# schematic.net
KiCad netlist of a schematic drawn in EAGLE
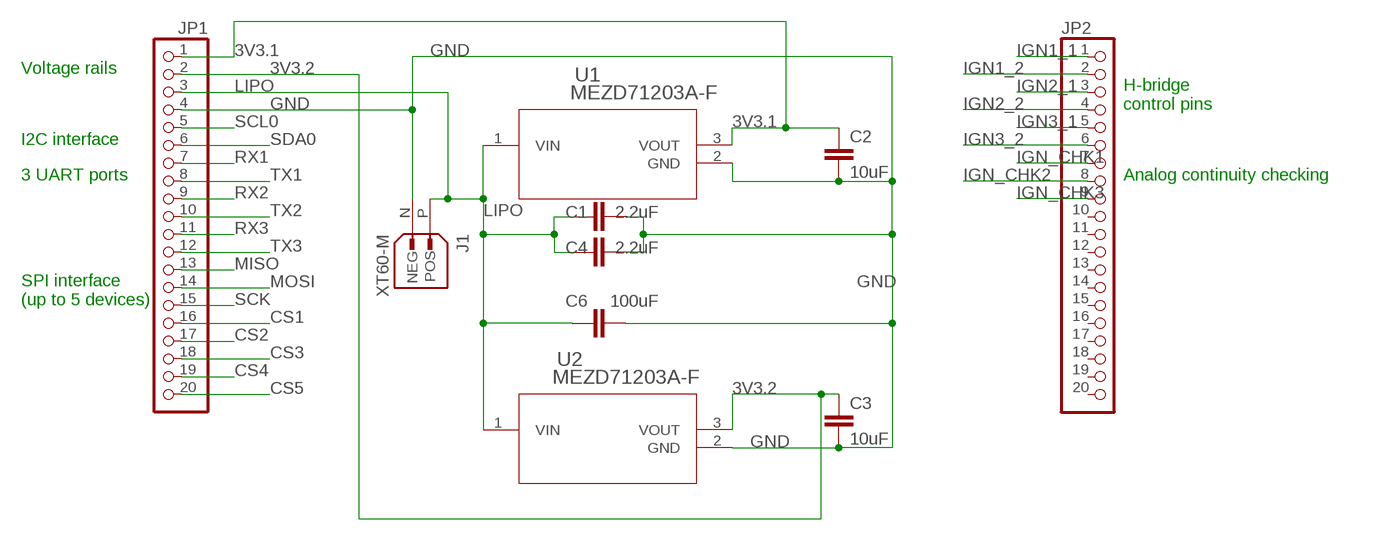
[diagram p0: schematic, sheet 1]

(export (version "E")
  (design (tool "Eeschema 10.0.6"))
  (components
    (comp (ref "C1")
      (value "2.2uF")
      (footprint "eagle-import:C0805")
      (libsource (lib "eagle-import") (part "C-EUC0805"))
    )
    (comp (ref "C2")
      (value "10uF")
      (footprint "eagle-import:C0805")
      (libsource (lib "eagle-import") (part "C-EUC0805"))
    )
    (comp (ref "C3")
      (value "10uF")
      (footprint "eagle-import:C0805")
      (libsource (lib "eagle-import") (part "C-EUC0805"))
    )
    (comp (ref "C4")
      (value "2.2uF")
      (footprint "eagle-import:C0805")
      (libsource (lib "eagle-import") (part "C-EUC0805"))
    )
    (comp (ref "C6")
      (value "100uF")
      (footprint "eagle-import:C0805")
      (libsource (lib "eagle-import") (part "C-EUC0805"))
    )
    (comp (ref "J1")
      (value "XT60-M")
      (footprint "eagle-import:AMASS_XT60-M")
      (fields (field (name "MF") "AMASS"))
      (libsource (lib "eagle-import") (part "XT60-M"))
    )
    (comp (ref "JP1")
      (value "PINHD-1X20")
      (footprint "eagle-import:1X20")
      (libsource (lib "eagle-import") (part "PINHD-1X20"))
    )
    (comp (ref "JP2")
      (value "PINHD-1X20")
      (footprint "eagle-import:1X20")
      (libsource (lib "eagle-import") (part "PINHD-1X20"))
    )
    (comp (ref "U1")
      (value "MEZD71203A-F")
      (footprint "eagle-import:MEZD71203A_MNP")
      (fields (field (name "COPYRIGHT") "Copyright (C) 2022 Ultra Librarian. All rights reserved."))
      (libsource (lib "eagle-import") (part "MEZD71203A-F"))
    )
    (comp (ref "U2")
      (value "MEZD71203A-F")
      (footprint "eagle-import:MEZD71203A_MNP")
      (fields (field (name "COPYRIGHT") "Copyright (C) 2022 Ultra Librarian. All rights reserved."))
      (libsource (lib "eagle-import") (part "MEZD71203A-F"))
    )
  )
  (nets
    (net (code "1") (name "/3V3.1") (class "Default")
      (node (ref "C2") (pin "1") (pinfunction "1_1") (pintype "passive"))
      (node (ref "JP1") (pin "1") (pinfunction "1_1") (pintype "passive"))
      (node (ref "U1") (pin "3") (pinfunction "VOUT_3") (pintype "output"))
    )
    (net (code "2") (name "/3V3.2") (class "Default")
      (node (ref "C3") (pin "1") (pinfunction "1_1") (pintype "passive"))
      (node (ref "JP1") (pin "2") (pinfunction "2_2") (pintype "passive"))
      (node (ref "U2") (pin "3") (pinfunction "VOUT_3") (pintype "output"))
    )
    (net (code "3") (name "/CS1") (class "Default")
      (node (ref "JP1") (pin "16") (pinfunction "16_16") (pintype "passive"))
    )
    (net (code "4") (name "/CS2") (class "Default")
      (node (ref "JP1") (pin "17") (pinfunction "17_17") (pintype "passive"))
    )
    (net (code "5") (name "/CS3") (class "Default")
      (node (ref "JP1") (pin "18") (pinfunction "18_18") (pintype "passive"))
    )
    (net (code "6") (name "/CS4") (class "Default")
      (node (ref "JP1") (pin "19") (pinfunction "19_19") (pintype "passive"))
    )
    (net (code "7") (name "/CS5") (class "Default")
      (node (ref "JP1") (pin "20") (pinfunction "20_20") (pintype "passive"))
    )
    (net (code "8") (name "/GND") (class "Default")
      (node (ref "C1") (pin "2") (pinfunction "2_2") (pintype "passive"))
      (node (ref "C2") (pin "2") (pinfunction "2_2") (pintype "passive"))
      (node (ref "C3") (pin "2") (pinfunction "2_2") (pintype "passive"))
      (node (ref "C4") (pin "2") (pinfunction "2_2") (pintype "passive"))
      (node (ref "C6") (pin "2") (pinfunction "2_2") (pintype "passive"))
      (node (ref "J1") (pin "N") (pinfunction "NEG_N") (pintype "passive"))
      (node (ref "JP1") (pin "4") (pinfunction "4_4") (pintype "passive"))
      (node (ref "U1") (pin "2") (pinfunction "GND_2") (pintype "power_in"))
      (node (ref "U2") (pin "2") (pinfunction "GND_2") (pintype "power_in"))
    )
    (net (code "9") (name "/IGN1_1") (class "Default")
      (node (ref "JP2") (pin "1") (pinfunction "1_1") (pintype "passive"))
    )
    (net (code "10") (name "/IGN1_2") (class "Default")
      (node (ref "JP2") (pin "2") (pinfunction "2_2") (pintype "passive"))
    )
    (net (code "11") (name "/IGN2_1") (class "Default")
      (node (ref "JP2") (pin "3") (pinfunction "3_3") (pintype "passive"))
    )
    (net (code "12") (name "/IGN2_2") (class "Default")
      (node (ref "JP2") (pin "4") (pinfunction "4_4") (pintype "passive"))
    )
    (net (code "13") (name "/IGN3_1") (class "Default")
      (node (ref "JP2") (pin "5") (pinfunction "5_5") (pintype "passive"))
    )
    (net (code "14") (name "/IGN3_2") (class "Default")
      (node (ref "JP2") (pin "6") (pinfunction "6_6") (pintype "passive"))
    )
    (net (code "15") (name "/IGN_CHK1") (class "Default")
      (node (ref "JP2") (pin "7") (pinfunction "7_7") (pintype "passive"))
    )
    (net (code "16") (name "/IGN_CHK2") (class "Default")
      (node (ref "JP2") (pin "8") (pinfunction "8_8") (pintype "passive"))
    )
    (net (code "17") (name "/IGN_CHK3") (class "Default")
      (node (ref "JP2") (pin "9") (pinfunction "9_9") (pintype "passive"))
    )
    (net (code "18") (name "/LIPO") (class "Default")
      (node (ref "C1") (pin "1") (pinfunction "1_1") (pintype "passive"))
      (node (ref "C4") (pin "1") (pinfunction "1_1") (pintype "passive"))
      (node (ref "C6") (pin "1") (pinfunction "1_1") (pintype "passive"))
      (node (ref "J1") (pin "P") (pinfunction "POS_P") (pintype "passive"))
      (node (ref "JP1") (pin "3") (pinfunction "3_3") (pintype "passive"))
      (node (ref "U1") (pin "1") (pinfunction "VIN_1") (pintype "input"))
      (node (ref "U2") (pin "1") (pinfunction "VIN_1") (pintype "input"))
    )
    (net (code "19") (name "/MISO") (class "Default")
      (node (ref "JP1") (pin "13") (pinfunction "13_13") (pintype "passive"))
    )
    (net (code "20") (name "/MOSI") (class "Default")
      (node (ref "JP1") (pin "14") (pinfunction "14_14") (pintype "passive"))
    )
    (net (code "21") (name "/RX1") (class "Default")
      (node (ref "JP1") (pin "7") (pinfunction "7_7") (pintype "passive"))
    )
    (net (code "22") (name "/RX2") (class "Default")
      (node (ref "JP1") (pin "9") (pinfunction "9_9") (pintype "passive"))
    )
    (net (code "23") (name "/RX3") (class "Default")
      (node (ref "JP1") (pin "11") (pinfunction "11_11") (pintype "passive"))
    )
    (net (code "24") (name "/SCK") (class "Default")
      (node (ref "JP1") (pin "15") (pinfunction "15_15") (pintype "passive"))
    )
    (net (code "25") (name "/SCL0") (class "Default")
      (node (ref "JP1") (pin "5") (pinfunction "5_5") (pintype "passive"))
    )
    (net (code "26") (name "/SDA0") (class "Default")
      (node (ref "JP1") (pin "6") (pinfunction "6_6") (pintype "passive"))
    )
    (net (code "27") (name "/TX1") (class "Default")
      (node (ref "JP1") (pin "8") (pinfunction "8_8") (pintype "passive"))
    )
    (net (code "28") (name "/TX2") (class "Default")
      (node (ref "JP1") (pin "10") (pinfunction "10_10") (pintype "passive"))
    )
    (net (code "29") (name "/TX3") (class "Default")
      (node (ref "JP1") (pin "12") (pinfunction "12_12") (pintype "passive"))
    )
    (net (code "30") (name "unconnected-(JP2-Pad10)") (class "Default")
      (node (ref "JP2") (pin "10") (pinfunction "10_10") (pintype "passive"))
    )
    (net (code "31") (name "unconnected-(JP2-Pad11)") (class "Default")
      (node (ref "JP2") (pin "11") (pinfunction "11_11") (pintype "passive"))
    )
    (net (code "32") (name "unconnected-(JP2-Pad12)") (class "Default")
      (node (ref "JP2") (pin "12") (pinfunction "12_12") (pintype "passive"))
    )
    (net (code "33") (name "unconnected-(JP2-Pad13)") (class "Default")
      (node (ref "JP2") (pin "13") (pinfunction "13_13") (pintype "passive"))
    )
    (net (code "34") (name "unconnected-(JP2-Pad14)") (class "Default")
      (node (ref "JP2") (pin "14") (pinfunction "14_14") (pintype "passive"))
    )
    (net (code "35") (name "unconnected-(JP2-Pad15)") (class "Default")
      (node (ref "JP2") (pin "15") (pinfunction "15_15") (pintype "passive"))
    )
    (net (code "36") (name "unconnected-(JP2-Pad16)") (class "Default")
      (node (ref "JP2") (pin "16") (pinfunction "16_16") (pintype "passive"))
    )
    (net (code "37") (name "unconnected-(JP2-Pad17)") (class "Default")
      (node (ref "JP2") (pin "17") (pinfunction "17_17") (pintype "passive"))
    )
    (net (code "38") (name "unconnected-(JP2-Pad18)") (class "Default")
      (node (ref "JP2") (pin "18") (pinfunction "18_18") (pintype "passive"))
    )
    (net (code "39") (name "unconnected-(JP2-Pad19)") (class "Default")
      (node (ref "JP2") (pin "19") (pinfunction "19_19") (pintype "passive"))
    )
    (net (code "40") (name "unconnected-(JP2-Pad20)") (class "Default")
      (node (ref "JP2") (pin "20") (pinfunction "20_20") (pintype "passive"))
    )
  )
)
